# mySensor.net
KiCad netlist of a schematic drawn in Altium Designer
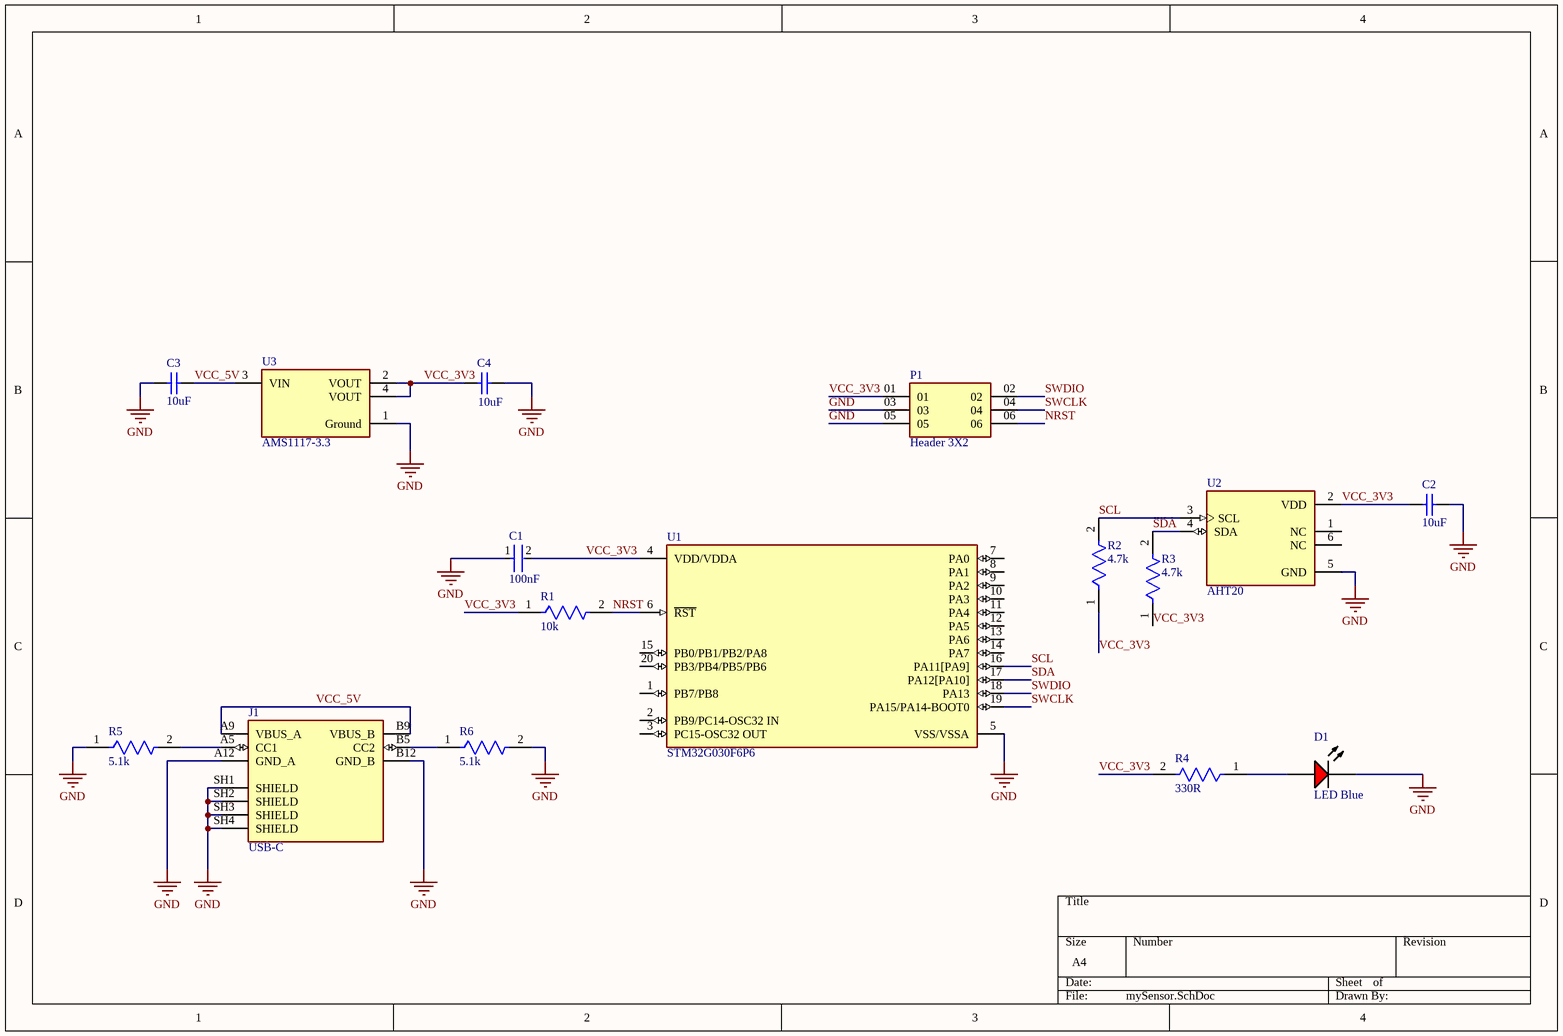
[diagram p0: mySensor.SchDoc]

(export (version "E")
  (design (tool "Eeschema 10.0.6"))
  (components
    (comp (ref "C1")
      (value "100nF")
      (footprint "FP-C1206C-EB-MFG")
      (description "CAP CER 0.1UF 50V X7R 1206")
      (fields
        (field (name "MANUFACTURER") "KEMET")
        (field (name "OCTOPART") "https://octopart.com/c1206c104k5racauto-kemet-12595586")
      )
      (libsource (lib "Altium Content Vault") (part "b4654b650e69147ec39a6b967a45e02"))
    )
    (comp (ref "C2")
      (value "10uF")
      (footprint "CAPC1206(3216)190_L")
      (description "CAP 10uF 6.3V ±20% 1206 (3216 Metric) Thickness 1.9mm SMD")
      (fields (field (name "TOLERANCE") "Â±20%"))
      (libsource (lib "Altium Content Vault") (part "CAP"))
    )
    (comp (ref "C3")
      (value "10uF")
      (footprint "CAPC1206(3216)190_L")
      (description "CAP 10uF 6.3V ±20% 1206 (3216 Metric) Thickness 1.9mm SMD")
      (fields (field (name "TOLERANCE") "Â±20%"))
      (libsource (lib "Altium Content Vault") (part "CAP"))
    )
    (comp (ref "C4")
      (value "10uF")
      (footprint "CAPC1206(3216)190_L")
      (description "CAP 10uF 6.3V ±20% 1206 (3216 Metric) Thickness 1.9mm SMD")
      (fields (field (name "TOLERANCE") "Â±20%"))
      (libsource (lib "Altium Content Vault") (part "CAP"))
    )
    (comp (ref "D1")
      (value "LED Blue")
      (footprint "LUMX-SML-LX1206IC_V")
      (description "LED Red, 65 mW, -40 to 85 degC, 2-Pin SMD, RoHS, Tape and Reel")
      (fields (field (name "MANUFACTURER") "Lumex") (field (name "PART NO") "SML-LX1206IC-TR"))
      (libsource (lib "Altium Content Vault") (part "LED-RED-AK-2"))
    )
    (comp (ref "J1")
      (value "USB-C")
      (footprint "AMPHENOL_10164359-00011LF")
      (description "USB Type C Receptacle SMT Single Row 6Pin")
      (fields (field (name "MF") "Amphenol") (field (name "MP") "1016435900011LF"))
      (libsource (lib "10164359-00011LF") (part "10164359-00011LF"))
    )
    (comp (ref "P1")
      (value "Header 3X2")
      (footprint "SAMTEC_TSM-103-02-T-DV-LC")
      (description "Conn Unshrouded Header HDR 6 POS 2.54mm Solder ST SMD Tube")
      (fields (field (name "MF") "Samtec") (field (name "MP") "TSM-103-02-T-DV-LC"))
      (libsource (lib "TSM-103-02-T-DV-LC") (part "TSM-103-02-T-DV-LC"))
    )
    (comp (ref "R1")
      (value "10k")
      (footprint "FP-CRGCQ1206-IPC_C")
      (description "CRGCQ1206 10KΩ 0.25W 1% ±100ppm/°C 200V")
      (fields (field (name "MANUFACTURER") "TE Connectivity") (field (name "TOLERANCE") "0.01"))
      (libsource (lib "Altium Content Vault") (part "1029c3af85768c4190bb7ad29bc67b5"))
    )
    (comp (ref "R2")
      (value "4.7k")
      (footprint "FP-CRGCQ1206-IPC_C")
      (description "CRGCQ 1206 4K7 5%")
      (fields
        (field (name "MANUFACTURER") "TE Connectivity")
        (field (name "OCTOPART") "https://octopart.com/crgcq1206j4k7-te+connectivity-91018336")
      )
      (libsource (lib "Altium Content Vault") (part "1029c3af85768c4190bb7ad29bc67b5"))
    )
    (comp (ref "R3")
      (value "4.7k")
      (footprint "FP-CRGCQ1206-IPC_C")
      (description "CRGCQ 1206 4K7 5%")
      (fields
        (field (name "MANUFACTURER") "TE Connectivity")
        (field (name "OCTOPART") "https://octopart.com/crgcq1206j4k7-te+connectivity-91018336")
      )
      (libsource (lib "Altium Content Vault") (part "1029c3af85768c4190bb7ad29bc67b5"))
    )
    (comp (ref "R4")
      (value "330R")
      (footprint "FP-RN73R2B-IPC_A")
      (description "330Ω ±0.1% 0.25W, 1/4W Chip Resistor 1206 (3216 Metric) Moisture Resistant Thin Film")
      (libsource (lib "Altium Content Vault") (part "1029c3af85768c4190bb7ad29bc67b5"))
    )
    (comp (ref "R5")
      (value "5.1k")
      (footprint "FP-CRCW0805-HPe3-IPC_B")
      (description "RES Thick Film, 5.1kΩ, 5%, 0.5W, 200ppm/°C, 0805")
      (fields (field (name "TOLERANCE") "5%"))
      (libsource (lib "Altium Content Vault") (part "1029c3af85768c4190bb7ad29bc67b5"))
    )
    (comp (ref "R6")
      (value "5.1k")
      (footprint "FP-CRCW0805-HPe3-IPC_B")
      (description "RES Thick Film, 5.1kΩ, 5%, 0.5W, 200ppm/°C, 0805")
      (fields (field (name "TOLERANCE") "5%"))
      (libsource (lib "Altium Content Vault") (part "1029c3af85768c4190bb7ad29bc67b5"))
    )
    (comp (ref "U1")
      (value "STM32G030F6P6")
      (footprint "FP-TSSOP20-YA-MFG")
      (description "ARM MICROCONTROLLERS - MCU")
      (fields
        (field (name "MANUFACTURER") "STMicroelectronics")
        (field (name "OCTOPART") "https://octopart.com/stm32g030f6p6-stmicroelectronics-103773023")
      )
      (libsource (lib "Altium Content Vault") (part "de2f7cf56ecdc1f1ec6ab3e49dbf5e6"))
    )
    (comp (ref "U2")
      (value "AHT20")
      (footprint "PSON100P300X300X110-6N")
      (description "Temperature and Humidity sensor")
      (fields (field (name "MF") "Asair"))
      (libsource (lib "AHT20") (part "AHT20"))
    )
    (comp (ref "U3")
      (value "AMS1117-3.3")
      (footprint "FP-AMS1117-IPC_C")
      (description "LDO Voltage Regulators 1A, 3.3V")
      (fields
        (field (name "OCTOPART") "https://octopart.com/ams1117-3.3-advanced+monolithic+systems-25899300")
        (field (name "MANUFACTURER") "Advanced Monolithic Systems")
      )
      (libsource (lib "Altium Content Vault") (part "8bdbb5f8e77002000e30dd2845d0354"))
    )
  )
  (nets
    (net (code "1") (name "/NRST") (class "Default")
      (node (ref "P1") (pin "06") (pinfunction "06_06") (pintype "passive"))
      (node (ref "R1") (pin "2") (pinfunction "2_2") (pintype "passive"))
      (node (ref "U1") (pin "6") (pinfunction "~{RST}_6") (pintype "input"))
    )
    (net (code "2") (name "/SCL") (class "Default")
      (node (ref "R2") (pin "2") (pinfunction "2_2") (pintype "passive"))
      (node (ref "U1") (pin "16") (pinfunction "PA11[PA9]_16") (pintype "bidirectional"))
      (node (ref "U2") (pin "3") (pinfunction "SCL_3") (pintype "input"))
    )
    (net (code "3") (name "/SDA") (class "Default")
      (node (ref "R3") (pin "2") (pinfunction "2_2") (pintype "passive"))
      (node (ref "U1") (pin "17") (pinfunction "PA12[PA10]_17") (pintype "bidirectional"))
      (node (ref "U2") (pin "4") (pinfunction "SDA_4") (pintype "bidirectional"))
    )
    (net (code "4") (name "/SWCLK") (class "Default")
      (node (ref "P1") (pin "04") (pinfunction "04_04") (pintype "passive"))
      (node (ref "U1") (pin "19") (pinfunction "PA15/PA14-BOOT0_19") (pintype "bidirectional"))
    )
    (net (code "5") (name "/SWDIO") (class "Default")
      (node (ref "P1") (pin "02") (pinfunction "02_02") (pintype "passive"))
      (node (ref "U1") (pin "18") (pinfunction "PA13_18") (pintype "bidirectional"))
    )
    (net (code "6") (name "/VCC_3V3") (class "Default")
      (node (ref "C1") (pin "2") (pinfunction "2_2") (pintype "passive"))
      (node (ref "C2") (pin "1") (pinfunction "1_1") (pintype "passive"))
      (node (ref "C4") (pin "1") (pinfunction "1_1") (pintype "passive"))
      (node (ref "P1") (pin "01") (pinfunction "01_01") (pintype "passive"))
      (node (ref "R1") (pin "1") (pinfunction "1_1") (pintype "passive"))
      (node (ref "R2") (pin "1") (pinfunction "1_1") (pintype "passive"))
      (node (ref "R3") (pin "1") (pinfunction "1_1") (pintype "passive"))
      (node (ref "R4") (pin "2") (pinfunction "2_2") (pintype "passive"))
      (node (ref "U1") (pin "4") (pinfunction "VDD/VDDA_4") (pintype "power_in"))
      (node (ref "U2") (pin "2") (pinfunction "VDD_2") (pintype "power_in"))
      (node (ref "U3") (pin "2") (pinfunction "VOUT_2") (pintype "passive"))
      (node (ref "U3") (pin "4") (pinfunction "VOUT_4") (pintype "passive"))
    )
    (net (code "7") (name "/VCC_5V") (class "Default")
      (node (ref "C3") (pin "2") (pinfunction "2_2") (pintype "passive"))
      (node (ref "J1") (pin "A9") (pinfunction "VBUS_A_A9") (pintype "power_in"))
      (node (ref "J1") (pin "B9") (pinfunction "VBUS_B_B9") (pintype "power_in"))
      (node (ref "U3") (pin "3") (pinfunction "VIN_3") (pintype "power_in"))
    )
    (net (code "8") (name "GND") (class "Default")
      (node (ref "C1") (pin "1") (pinfunction "1_1") (pintype "passive"))
      (node (ref "C2") (pin "2") (pinfunction "2_2") (pintype "passive"))
      (node (ref "C3") (pin "1") (pinfunction "1_1") (pintype "passive"))
      (node (ref "C4") (pin "2") (pinfunction "2_2") (pintype "passive"))
      (node (ref "D1") (pin "2") (pinfunction "K_2") (pintype "passive"))
      (node (ref "J1") (pin "A12") (pinfunction "GND_A_A12") (pintype "power_in"))
      (node (ref "J1") (pin "B12") (pinfunction "GND_B_B12") (pintype "power_in"))
      (node (ref "J1") (pin "SH1") (pinfunction "SHIELD_SH1") (pintype "passive"))
      (node (ref "J1") (pin "SH2") (pinfunction "SHIELD_SH2") (pintype "passive"))
      (node (ref "J1") (pin "SH3") (pinfunction "SHIELD_SH3") (pintype "passive"))
      (node (ref "J1") (pin "SH4") (pinfunction "SHIELD_SH4") (pintype "passive"))
      (node (ref "P1") (pin "03") (pinfunction "03_03") (pintype "passive"))
      (node (ref "P1") (pin "05") (pinfunction "05_05") (pintype "passive"))
      (node (ref "R5") (pin "1") (pinfunction "1_1") (pintype "passive"))
      (node (ref "R6") (pin "2") (pinfunction "2_2") (pintype "passive"))
      (node (ref "U1") (pin "5") (pinfunction "VSS/VSSA_5") (pintype "power_in"))
      (node (ref "U2") (pin "5") (pinfunction "GND_5") (pintype "power_in"))
      (node (ref "U3") (pin "1") (pinfunction "Ground_1") (pintype "power_in"))
    )
    (net (code "9") (name "Net-(D1-A)") (class "Default")
      (node (ref "D1") (pin "1") (pinfunction "A_1") (pintype "passive"))
      (node (ref "R4") (pin "1") (pinfunction "1_1") (pintype "passive"))
    )
    (net (code "10") (name "Net-(J1-CC1)") (class "Default")
      (node (ref "J1") (pin "A5") (pinfunction "CC1_A5") (pintype "bidirectional"))
      (node (ref "R5") (pin "2") (pinfunction "2_2") (pintype "passive"))
    )
    (net (code "11") (name "Net-(J1-CC2)") (class "Default")
      (node (ref "J1") (pin "B5") (pinfunction "CC2_B5") (pintype "bidirectional"))
      (node (ref "R6") (pin "1") (pinfunction "1_1") (pintype "passive"))
    )
    (net (code "12") (name "unconnected-(U1-PA0-Pad7)") (class "Default")
      (node (ref "U1") (pin "7") (pinfunction "PA0_7") (pintype "bidirectional"))
    )
    (net (code "13") (name "unconnected-(U1-PA1-Pad8)") (class "Default")
      (node (ref "U1") (pin "8") (pinfunction "PA1_8") (pintype "bidirectional"))
    )
    (net (code "14") (name "unconnected-(U1-PA2-Pad9)") (class "Default")
      (node (ref "U1") (pin "9") (pinfunction "PA2_9") (pintype "bidirectional"))
    )
    (net (code "15") (name "unconnected-(U1-PA3-Pad10)") (class "Default")
      (node (ref "U1") (pin "10") (pinfunction "PA3_10") (pintype "bidirectional"))
    )
    (net (code "16") (name "unconnected-(U1-PA4-Pad11)") (class "Default")
      (node (ref "U1") (pin "11") (pinfunction "PA4_11") (pintype "bidirectional"))
    )
    (net (code "17") (name "unconnected-(U1-PA5-Pad12)") (class "Default")
      (node (ref "U1") (pin "12") (pinfunction "PA5_12") (pintype "bidirectional"))
    )
    (net (code "18") (name "unconnected-(U1-PA6-Pad13)") (class "Default")
      (node (ref "U1") (pin "13") (pinfunction "PA6_13") (pintype "bidirectional"))
    )
    (net (code "19") (name "unconnected-(U1-PA7-Pad14)") (class "Default")
      (node (ref "U1") (pin "14") (pinfunction "PA7_14") (pintype "bidirectional"))
    )
    (net (code "20") (name "unconnected-(U1-PB0{slash}PB1{slash}PB2{slash}PA8-Pad15)") (class "Default")
      (node (ref "U1") (pin "15") (pinfunction "PB0/PB1/PB2/PA8_15") (pintype "bidirectional"))
    )
    (net (code "21") (name "unconnected-(U1-PB3{slash}PB4{slash}PB5{slash}PB6-Pad20)") (class "Default")
      (node (ref "U1") (pin "20") (pinfunction "PB3/PB4/PB5/PB6_20") (pintype "bidirectional"))
    )
    (net (code "22") (name "unconnected-(U1-PB7{slash}PB8-Pad1)") (class "Default")
      (node (ref "U1") (pin "1") (pinfunction "PB7/PB8_1") (pintype "bidirectional"))
    )
    (net (code "23") (name "unconnected-(U1-PB9{slash}PC14-OSC32_IN-Pad2)") (class "Default")
      (node (ref "U1") (pin "2") (pinfunction "PB9/PC14-OSC32_IN_2") (pintype "bidirectional"))
    )
    (net (code "24") (name "unconnected-(U1-PC15-OSC32_OUT-Pad3)") (class "Default")
      (node (ref "U1") (pin "3") (pinfunction "PC15-OSC32_OUT_3") (pintype "bidirectional"))
    )
    (net (code "25") (name "unconnected-(U2-NC-Pad1)") (class "Default")
      (node (ref "U2") (pin "1") (pinfunction "NC_1") (pintype "passive"))
    )
    (net (code "26") (name "unconnected-(U2-NC-Pad6)") (class "Default")
      (node (ref "U2") (pin "6") (pinfunction "NC_6") (pintype "passive"))
    )
  )
)
